# local_light.net
KiCad netlist of a schematic drawn in EAGLE
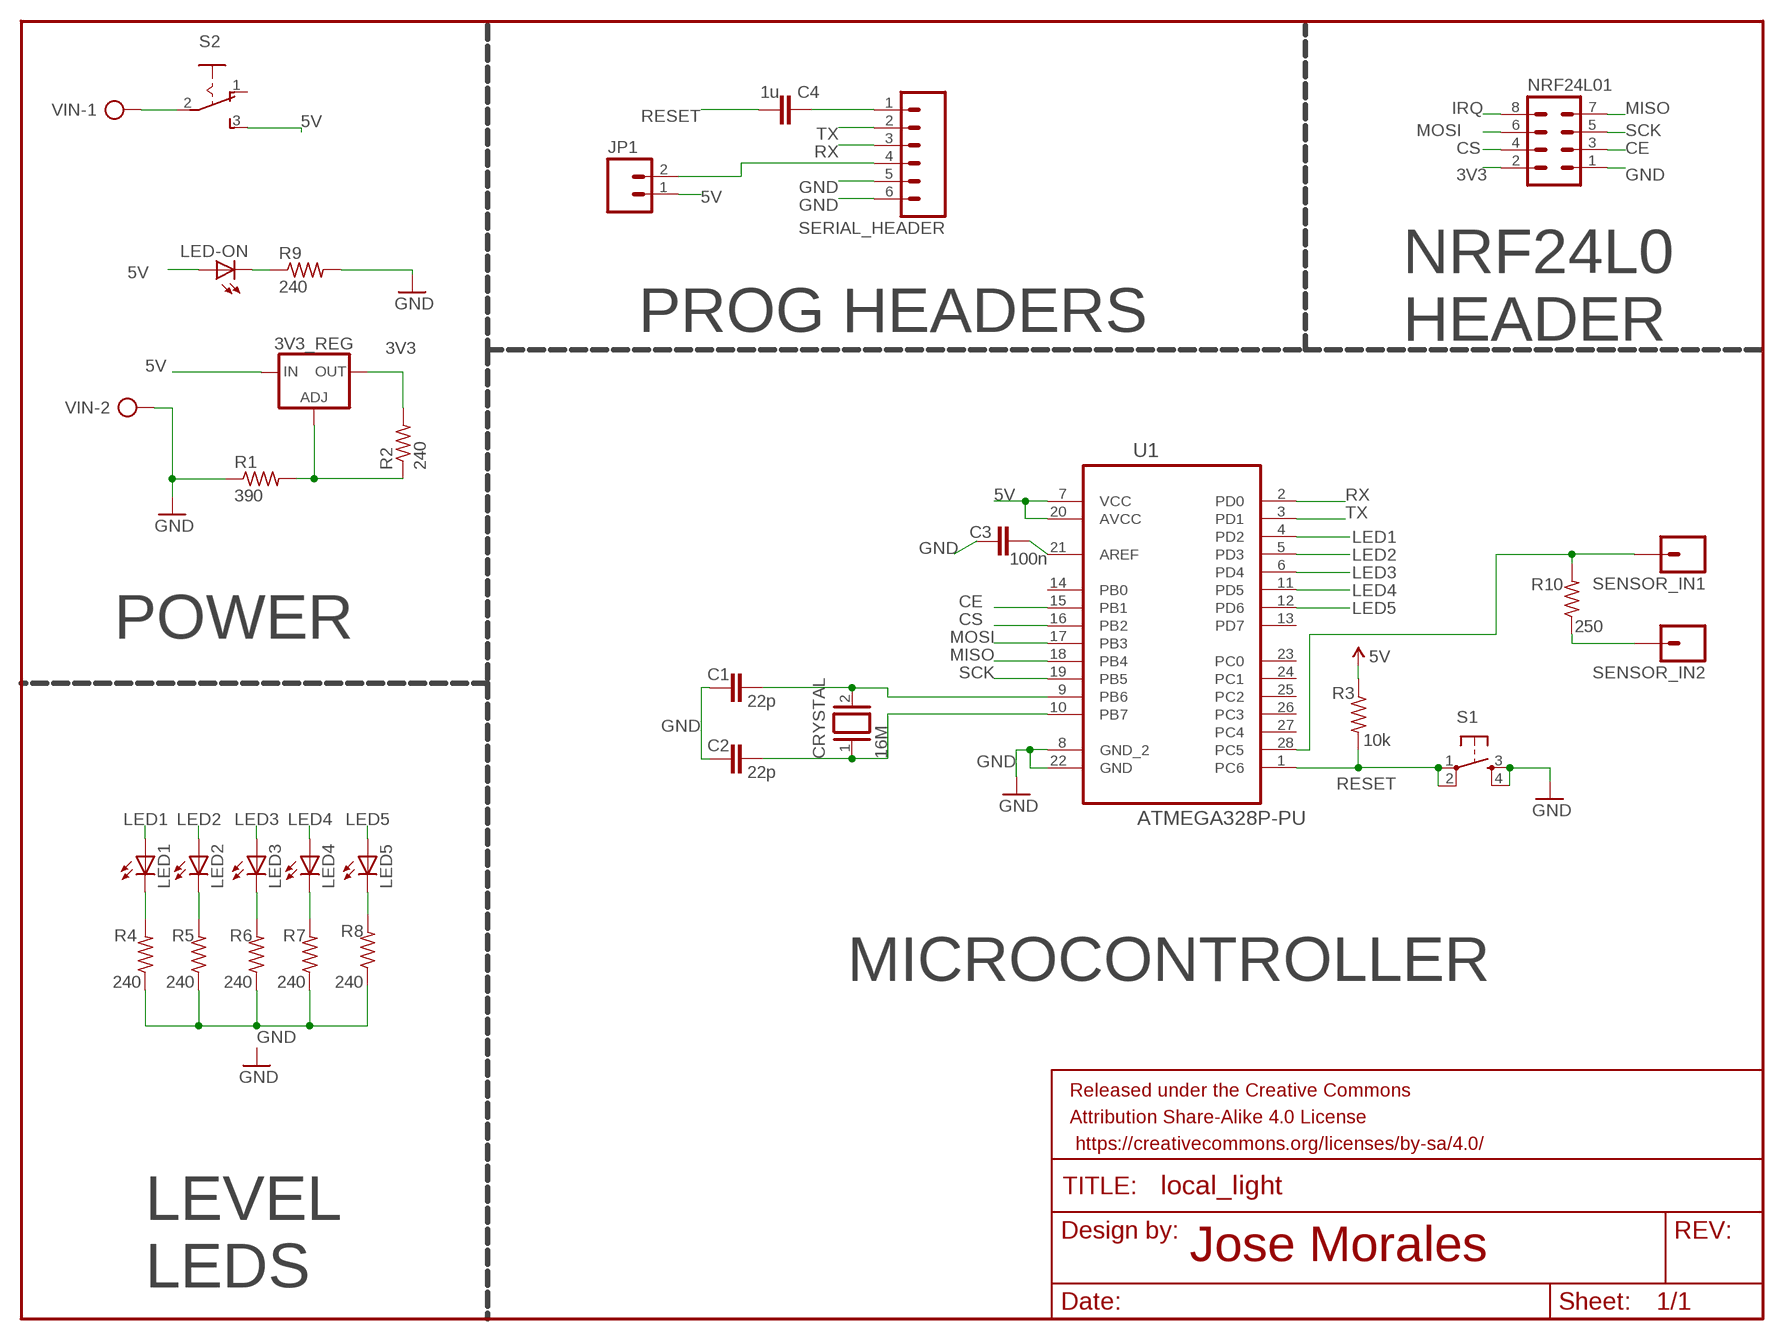
[diagram p0: schematic, sheet 1]

(export (version "E")
  (design (tool "Eeschema 10.0.6"))
  (components
    (comp (ref "C1")
      (value "22p")
      (footprint "eagle-import:C050-025X075")
      (libsource (lib "eagle-import") (part "C-EU050-025X075"))
    )
    (comp (ref "C2")
      (value "22p")
      (footprint "eagle-import:C050-025X075")
      (libsource (lib "eagle-import") (part "C-EU050-025X075"))
    )
    (comp (ref "C3")
      (value "100n")
      (footprint "eagle-import:C050-025X075")
      (libsource (lib "eagle-import") (part "C-EU050-025X075"))
    )
    (comp (ref "C4")
      (value "1u")
      (footprint "eagle-import:C050-025X075")
      (libsource (lib "eagle-import") (part "C-EU050-025X075"))
    )
    (comp (ref "CRYSTAL")
      (value "16M")
      (footprint "eagle-import:QS")
      (libsource (lib "eagle-import") (part "XTAL/S"))
    )
    (comp (ref "FRAME11")
      (value "FRAME-LETTER")
      (footprint "eagle-import:CREATIVE_COMMONS")
      (fields (field (name "DESIGNER") "NAME"))
      (libsource (lib "eagle-import") (part "FRAME-LETTER"))
    )
    (comp (ref "JP1")
      (value "M02LOCK")
      (footprint "eagle-import:1X02_LOCK")
      (libsource (lib "eagle-import") (part "M02LOCK"))
    )
    (comp (ref "LED-ON")
      (value "LED5MM")
      (footprint "eagle-import:LED5MM")
      (libsource (lib "eagle-import") (part "LED5MM"))
    )
    (comp (ref "LED1")
      (value "LED5MM")
      (footprint "eagle-import:LED5MM")
      (libsource (lib "eagle-import") (part "LED5MM"))
    )
    (comp (ref "LED2")
      (value "LED5MM")
      (footprint "eagle-import:LED5MM")
      (libsource (lib "eagle-import") (part "LED5MM"))
    )
    (comp (ref "LED3")
      (value "LED5MM")
      (footprint "eagle-import:LED5MM")
      (libsource (lib "eagle-import") (part "LED5MM"))
    )
    (comp (ref "LED4")
      (value "LED5MM")
      (footprint "eagle-import:LED5MM")
      (libsource (lib "eagle-import") (part "LED5MM"))
    )
    (comp (ref "LED5")
      (value "LED5MM")
      (footprint "eagle-import:LED5MM")
      (libsource (lib "eagle-import") (part "LED5MM"))
    )
    (comp (ref "LM317")
      (value "3V3_REG")
      (footprint "eagle-import:317TS")
      (libsource (lib "eagle-import") (part "LM317TS"))
    )
    (comp (ref "NRF24L01")
      (value "MA04-2")
      (footprint "eagle-import:MA04-2")
      (libsource (lib "eagle-import") (part "MA04-2"))
    )
    (comp (ref "R1")
      (value "390")
      (footprint "eagle-import:0207_12")
      (libsource (lib "eagle-import") (part "R-US_0207/12"))
    )
    (comp (ref "R2")
      (value "240")
      (footprint "eagle-import:0207_12")
      (libsource (lib "eagle-import") (part "R-US_0207/12"))
    )
    (comp (ref "R3")
      (value "10k")
      (footprint "eagle-import:0207_12")
      (libsource (lib "eagle-import") (part "R-US_0207/12"))
    )
    (comp (ref "R4")
      (value "240")
      (footprint "eagle-import:0207_12")
      (libsource (lib "eagle-import") (part "R-US_0207/12"))
    )
    (comp (ref "R5")
      (value "240")
      (footprint "eagle-import:0207_12")
      (libsource (lib "eagle-import") (part "R-US_0207/12"))
    )
    (comp (ref "R6")
      (value "240")
      (footprint "eagle-import:0207_12")
      (libsource (lib "eagle-import") (part "R-US_0207/12"))
    )
    (comp (ref "R7")
      (value "240")
      (footprint "eagle-import:0207_12")
      (libsource (lib "eagle-import") (part "R-US_0207/12"))
    )
    (comp (ref "R8")
      (value "240")
      (footprint "eagle-import:0207_12")
      (libsource (lib "eagle-import") (part "R-US_0207/12"))
    )
    (comp (ref "R9")
      (value "240")
      (footprint "eagle-import:0207_12")
      (libsource (lib "eagle-import") (part "R-US_0207/12"))
    )
    (comp (ref "R10")
      (value "250")
      (footprint "eagle-import:0207_12")
      (libsource (lib "eagle-import") (part "R-US_0207/12"))
    )
    (comp (ref "S1")
      (value "TAC_SWITCHPTH")
      (footprint "eagle-import:TACTILE-PTH")
      (libsource (lib "eagle-import") (part "TAC_SWITCHPTH"))
    )
    (comp (ref "S2")
      (value "255SB")
      (footprint "eagle-import:255SB")
      (libsource (lib "eagle-import") (part "255SB"))
    )
    (comp (ref "SENSOR_IN1")
      (value "M01PTH")
      (footprint "eagle-import:1X01")
      (libsource (lib "eagle-import") (part "M01PTH"))
    )
    (comp (ref "SENSOR_IN2")
      (value "M01PTH")
      (footprint "eagle-import:1X01")
      (libsource (lib "eagle-import") (part "M01PTH"))
    )
    (comp (ref "SERIAL_HEADER")
      (value "M06POLAR")
      (footprint "eagle-import:MOLEX-1X6")
      (libsource (lib "eagle-import") (part "M06POLAR"))
    )
    (comp (ref "U1")
      (value "ATMEGA328P-PU")
      (footprint "eagle-import:DIP254P762X457-28")
      (libsource (lib "eagle-import") (part "ATMEGA328P-PU"))
    )
    (comp (ref "VIN")
      (value "AK300/2")
      (footprint "eagle-import:AK300_2")
      (libsource (lib "eagle-import") (part "AK300/2"))
    )
  )
  (nets
    (net (code "1") (name "/3V3") (class "Default")
      (node (ref "LM317") (pin "2") (pinfunction "OUT_2") (pintype "passive"))
      (node (ref "NRF24L01") (pin "2") (pinfunction "2_2") (pintype "passive"))
      (node (ref "R2") (pin "2") (pinfunction "2_2") (pintype "passive"))
    )
    (net (code "2") (name "/CE") (class "Default")
      (node (ref "NRF24L01") (pin "3") (pinfunction "3_3") (pintype "passive"))
      (node (ref "U1") (pin "15") (pinfunction "PB1_15") (pintype "bidirectional"))
    )
    (net (code "3") (name "/CS") (class "Default")
      (node (ref "NRF24L01") (pin "4") (pinfunction "4_4") (pintype "passive"))
      (node (ref "U1") (pin "16") (pinfunction "PB2_16") (pintype "bidirectional"))
    )
    (net (code "4") (name "/IRQ") (class "Default")
      (node (ref "NRF24L01") (pin "8") (pinfunction "8_8") (pintype "passive"))
    )
    (net (code "5") (name "/LED1") (class "Default")
      (node (ref "LED1") (pin "A") (pinfunction "A_A") (pintype "passive"))
      (node (ref "U1") (pin "4") (pinfunction "PD2_4") (pintype "bidirectional"))
    )
    (net (code "6") (name "/LED2") (class "Default")
      (node (ref "LED2") (pin "A") (pinfunction "A_A") (pintype "passive"))
      (node (ref "U1") (pin "5") (pinfunction "PD3_5") (pintype "bidirectional"))
    )
    (net (code "7") (name "/LED3") (class "Default")
      (node (ref "LED3") (pin "A") (pinfunction "A_A") (pintype "passive"))
      (node (ref "U1") (pin "6") (pinfunction "PD4_6") (pintype "bidirectional"))
    )
    (net (code "8") (name "/LED4") (class "Default")
      (node (ref "LED4") (pin "A") (pinfunction "A_A") (pintype "passive"))
      (node (ref "U1") (pin "11") (pinfunction "PD5_11") (pintype "bidirectional"))
    )
    (net (code "9") (name "/LED5") (class "Default")
      (node (ref "LED5") (pin "A") (pinfunction "A_A") (pintype "passive"))
      (node (ref "U1") (pin "12") (pinfunction "PD6_12") (pintype "bidirectional"))
    )
    (net (code "10") (name "/MISO") (class "Default")
      (node (ref "NRF24L01") (pin "7") (pinfunction "7_7") (pintype "passive"))
      (node (ref "U1") (pin "18") (pinfunction "PB4_18") (pintype "bidirectional"))
    )
    (net (code "11") (name "/MOSI") (class "Default")
      (node (ref "NRF24L01") (pin "6") (pinfunction "6_6") (pintype "passive"))
      (node (ref "U1") (pin "17") (pinfunction "PB3_17") (pintype "bidirectional"))
    )
    (net (code "12") (name "/RESET") (class "Default")
      (node (ref "C4") (pin "1") (pinfunction "1_1") (pintype "passive"))
      (node (ref "R3") (pin "2") (pinfunction "2_2") (pintype "passive"))
      (node (ref "S1") (pin "1") (pinfunction "1_1") (pintype "passive"))
      (node (ref "S1") (pin "2") (pinfunction "2_2") (pintype "passive"))
      (node (ref "U1") (pin "1") (pinfunction "PC6_1") (pintype "bidirectional"))
    )
    (net (code "13") (name "/RX") (class "Default")
      (node (ref "SERIAL_HEADER") (pin "3") (pinfunction "3_3") (pintype "passive"))
      (node (ref "U1") (pin "2") (pinfunction "PD0_2") (pintype "bidirectional"))
    )
    (net (code "14") (name "/SCK") (class "Default")
      (node (ref "NRF24L01") (pin "5") (pinfunction "5_5") (pintype "passive"))
      (node (ref "U1") (pin "19") (pinfunction "PB5_19") (pintype "bidirectional"))
    )
    (net (code "15") (name "/TX") (class "Default")
      (node (ref "SERIAL_HEADER") (pin "2") (pinfunction "2_2") (pintype "passive"))
      (node (ref "U1") (pin "3") (pinfunction "PD1_3") (pintype "bidirectional"))
    )
    (net (code "16") (name "5V") (class "Default")
      (node (ref "JP1") (pin "1") (pinfunction "1_1") (pintype "passive"))
      (node (ref "LED-ON") (pin "A") (pinfunction "A_A") (pintype "passive"))
      (node (ref "LM317") (pin "3") (pinfunction "IN_3") (pintype "input"))
      (node (ref "R3") (pin "1") (pinfunction "1_1") (pintype "passive"))
      (node (ref "S2") (pin "3") (pinfunction "S_3") (pintype "passive"))
      (node (ref "U1") (pin "20") (pinfunction "AVCC_20") (pintype "power_in"))
      (node (ref "U1") (pin "7") (pinfunction "VCC_7") (pintype "power_in"))
    )
    (net (code "17") (name "GND") (class "Default")
      (node (ref "C1") (pin "2") (pinfunction "2_2") (pintype "passive"))
      (node (ref "C2") (pin "2") (pinfunction "2_2") (pintype "passive"))
      (node (ref "C3") (pin "2") (pinfunction "2_2") (pintype "passive"))
      (node (ref "NRF24L01") (pin "1") (pinfunction "1_1") (pintype "passive"))
      (node (ref "R1") (pin "1") (pinfunction "1_1") (pintype "passive"))
      (node (ref "R4") (pin "1") (pinfunction "1_1") (pintype "passive"))
      (node (ref "R5") (pin "1") (pinfunction "1_1") (pintype "passive"))
      (node (ref "R6") (pin "1") (pinfunction "1_1") (pintype "passive"))
      (node (ref "R7") (pin "1") (pinfunction "1_1") (pintype "passive"))
      (node (ref "R8") (pin "1") (pinfunction "1_1") (pintype "passive"))
      (node (ref "R9") (pin "2") (pinfunction "2_2") (pintype "passive"))
      (node (ref "S1") (pin "3") (pinfunction "3_3") (pintype "passive"))
      (node (ref "S1") (pin "4") (pinfunction "4_4") (pintype "passive"))
      (node (ref "SERIAL_HEADER") (pin "5") (pinfunction "5_5") (pintype "passive"))
      (node (ref "SERIAL_HEADER") (pin "6") (pinfunction "6_6") (pintype "passive"))
      (node (ref "U1") (pin "22") (pinfunction "GND_22") (pintype "passive"))
      (node (ref "U1") (pin "8") (pinfunction "GND_2_8") (pintype "passive"))
      (node (ref "VIN") (pin "2") (pinfunction "KL_2") (pintype "passive"))
    )
    (net (code "18") (name "Net-(C4-Pad2)") (class "Default")
      (node (ref "C4") (pin "2") (pinfunction "2_2") (pintype "passive"))
      (node (ref "SERIAL_HEADER") (pin "1") (pinfunction "1_1") (pintype "passive"))
    )
    (net (code "19") (name "Net-(JP1-Pad2)") (class "Default")
      (node (ref "JP1") (pin "2") (pinfunction "2_2") (pintype "passive"))
      (node (ref "SERIAL_HEADER") (pin "4") (pinfunction "4_4") (pintype "passive"))
    )
    (net (code "20") (name "Net-(LED-ON-C)") (class "Default")
      (node (ref "LED-ON") (pin "K") (pinfunction "C_K") (pintype "passive"))
      (node (ref "R9") (pin "1") (pinfunction "1_1") (pintype "passive"))
    )
    (net (code "21") (name "Net-(LED1-C)") (class "Default")
      (node (ref "LED1") (pin "K") (pinfunction "C_K") (pintype "passive"))
      (node (ref "R4") (pin "2") (pinfunction "2_2") (pintype "passive"))
    )
    (net (code "22") (name "Net-(LED2-C)") (class "Default")
      (node (ref "LED2") (pin "K") (pinfunction "C_K") (pintype "passive"))
      (node (ref "R5") (pin "2") (pinfunction "2_2") (pintype "passive"))
    )
    (net (code "23") (name "Net-(LED3-C)") (class "Default")
      (node (ref "LED3") (pin "K") (pinfunction "C_K") (pintype "passive"))
      (node (ref "R6") (pin "2") (pinfunction "2_2") (pintype "passive"))
    )
    (net (code "24") (name "Net-(LED4-C)") (class "Default")
      (node (ref "LED4") (pin "K") (pinfunction "C_K") (pintype "passive"))
      (node (ref "R7") (pin "2") (pinfunction "2_2") (pintype "passive"))
    )
    (net (code "25") (name "Net-(LED5-C)") (class "Default")
      (node (ref "LED5") (pin "K") (pinfunction "C_K") (pintype "passive"))
      (node (ref "R8") (pin "2") (pinfunction "2_2") (pintype "passive"))
    )
    (net (code "26") (name "Net-(LM317-ADJ)") (class "Default")
      (node (ref "LM317") (pin "1") (pinfunction "ADJ_1") (pintype "input"))
      (node (ref "R1") (pin "2") (pinfunction "2_2") (pintype "passive"))
      (node (ref "R2") (pin "1") (pinfunction "1_1") (pintype "passive"))
    )
    (net (code "27") (name "Net-(R10-Pad1)") (class "Default")
      (node (ref "R10") (pin "1") (pinfunction "1_1") (pintype "passive"))
      (node (ref "SENSOR_IN2") (pin "1") (pinfunction "1_1") (pintype "passive"))
    )
    (net (code "28") (name "Net-(S2-P)") (class "Default")
      (node (ref "S2") (pin "2") (pinfunction "P_2") (pintype "passive"))
      (node (ref "VIN") (pin "1") (pinfunction "KL_1") (pintype "passive"))
    )
    (net (code "29") (name "Net-(U1-AREF)") (class "Default")
      (node (ref "C3") (pin "1") (pinfunction "1_1") (pintype "passive"))
      (node (ref "U1") (pin "21") (pinfunction "AREF_21") (pintype "input"))
    )
    (net (code "30") (name "Net-(U1-PB6)") (class "Default")
      (node (ref "C1") (pin "1") (pinfunction "1_1") (pintype "passive"))
      (node (ref "CRYSTAL") (pin "2") (pinfunction "2_2") (pintype "passive"))
      (node (ref "U1") (pin "9") (pinfunction "PB6_9") (pintype "bidirectional"))
    )
    (net (code "31") (name "Net-(U1-PB7)") (class "Default")
      (node (ref "C2") (pin "1") (pinfunction "1_1") (pintype "passive"))
      (node (ref "CRYSTAL") (pin "1") (pinfunction "1_1") (pintype "passive"))
      (node (ref "U1") (pin "10") (pinfunction "PB7_10") (pintype "bidirectional"))
    )
    (net (code "32") (name "Net-(U1-PC5)") (class "Default")
      (node (ref "R10") (pin "2") (pinfunction "2_2") (pintype "passive"))
      (node (ref "SENSOR_IN1") (pin "1") (pinfunction "1_1") (pintype "passive"))
      (node (ref "U1") (pin "28") (pinfunction "PC5_28") (pintype "bidirectional"))
    )
    (net (code "33") (name "unconnected-(S2-O-Pad1)") (class "Default")
      (node (ref "S2") (pin "1") (pinfunction "O_1") (pintype "passive"))
    )
    (net (code "34") (name "unconnected-(U1-PB0-Pad14)") (class "Default")
      (node (ref "U1") (pin "14") (pinfunction "PB0_14") (pintype "bidirectional"))
    )
    (net (code "35") (name "unconnected-(U1-PC0-Pad23)") (class "Default")
      (node (ref "U1") (pin "23") (pinfunction "PC0_23") (pintype "bidirectional"))
    )
    (net (code "36") (name "unconnected-(U1-PC1-Pad24)") (class "Default")
      (node (ref "U1") (pin "24") (pinfunction "PC1_24") (pintype "bidirectional"))
    )
    (net (code "37") (name "unconnected-(U1-PC2-Pad25)") (class "Default")
      (node (ref "U1") (pin "25") (pinfunction "PC2_25") (pintype "bidirectional"))
    )
    (net (code "38") (name "unconnected-(U1-PC3-Pad26)") (class "Default")
      (node (ref "U1") (pin "26") (pinfunction "PC3_26") (pintype "bidirectional"))
    )
    (net (code "39") (name "unconnected-(U1-PC4-Pad27)") (class "Default")
      (node (ref "U1") (pin "27") (pinfunction "PC4_27") (pintype "bidirectional"))
    )
    (net (code "40") (name "unconnected-(U1-PD7-Pad13)") (class "Default")
      (node (ref "U1") (pin "13") (pinfunction "PD7_13") (pintype "bidirectional"))
    )
  )
)
